# remote.net
KiCad netlist of a schematic drawn in EAGLE
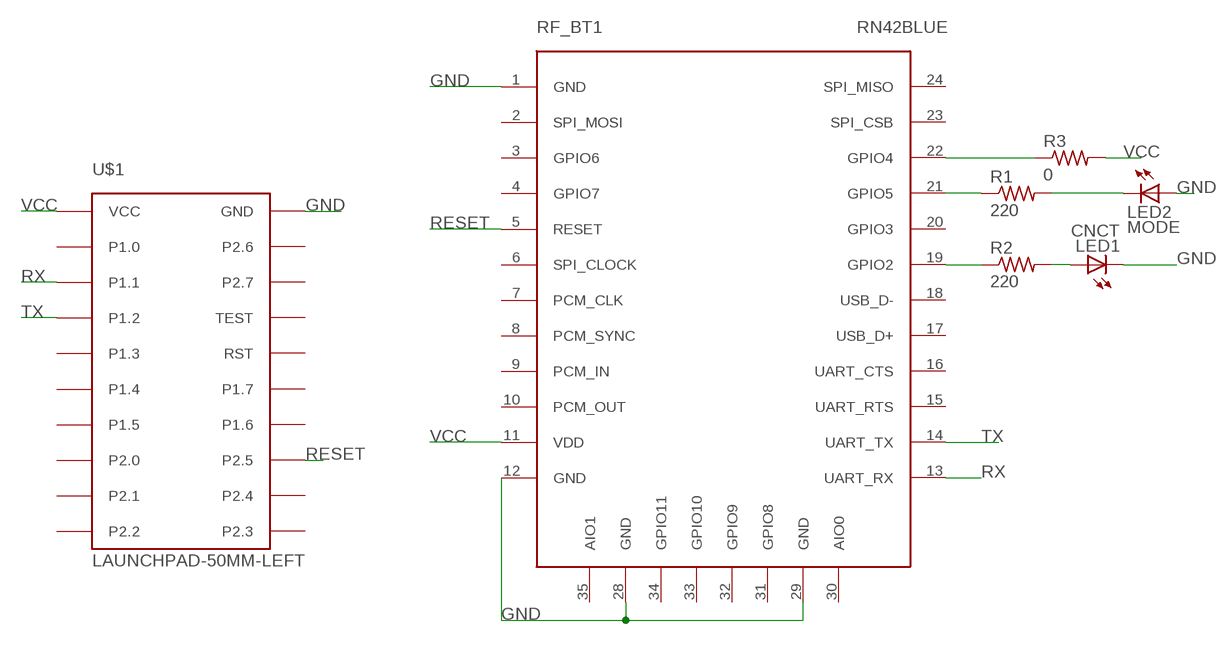
[diagram p0: schematic, sheet 1]

(export (version "E")
  (design (tool "Eeschema 10.0.6"))
  (components
    (comp (ref "LED1")
      (value "CNCT")
      (footprint "eagle-import:CHIPLED_0603")
      (libsource (lib "eagle-import") (part "LEDCHIPLED_0603"))
    )
    (comp (ref "LED2")
      (value "MODE")
      (footprint "eagle-import:CHIPLED_0603")
      (libsource (lib "eagle-import") (part "LEDCHIPLED_0603"))
    )
    (comp (ref "R1")
      (value "220")
      (footprint "eagle-import:R0603")
      (libsource (lib "eagle-import") (part "R-US_R0603"))
    )
    (comp (ref "R2")
      (value "220")
      (footprint "eagle-import:R0603")
      (libsource (lib "eagle-import") (part "R-US_R0603"))
    )
    (comp (ref "R3")
      (value "0")
      (footprint "eagle-import:R0603")
      (libsource (lib "eagle-import") (part "R-US_R0603"))
    )
    (comp (ref "RF_BT1")
      (value "RN42BLUE")
      (footprint "eagle-import:RN42_CUST_PAK")
      (libsource (lib "eagle-import") (part "RN42BLUE"))
    )
    (comp (ref "U$1")
      (value "LAUNCHPAD-50MM-LEFT")
      (footprint "eagle-import:LAUNCHPAD-50MM-LEFT")
      (libsource (lib "eagle-import") (part "LAUNCHPAD-50MM-LEFT"))
    )
  )
  (nets
    (net (code "1") (name "/GND") (class "Default")
      (node (ref "LED1") (pin "C") (pinfunction "C_C") (pintype "passive"))
      (node (ref "LED2") (pin "A") (pinfunction "A_A") (pintype "passive"))
      (node (ref "RF_BT1") (pin "1") (pinfunction "GND_1") (pintype "power_in"))
      (node (ref "RF_BT1") (pin "12") (pinfunction "GND_12") (pintype "power_in"))
      (node (ref "RF_BT1") (pin "28") (pinfunction "GND_28") (pintype "power_in"))
      (node (ref "RF_BT1") (pin "29") (pinfunction "GND_29") (pintype "power_in"))
      (node (ref "U$1") (pin "GND") (pinfunction "GND_GND") (pintype "power_in"))
    )
    (net (code "2") (name "/RESET") (class "Default")
      (node (ref "RF_BT1") (pin "5") (pinfunction "RESET_5") (pintype "bidirectional"))
      (node (ref "U$1") (pin "P2.5") (pinfunction "P2.5_P2.5") (pintype "bidirectional"))
    )
    (net (code "3") (name "/RX") (class "Default")
      (node (ref "RF_BT1") (pin "13") (pinfunction "UART_RX_13") (pintype "bidirectional"))
      (node (ref "U$1") (pin "P1.1") (pinfunction "P1.1_P1.1") (pintype "bidirectional"))
    )
    (net (code "4") (name "/TX") (class "Default")
      (node (ref "RF_BT1") (pin "14") (pinfunction "UART_TX_14") (pintype "bidirectional"))
      (node (ref "U$1") (pin "P1.2") (pinfunction "P1.2_P1.2") (pintype "bidirectional"))
    )
    (net (code "5") (name "/VCC") (class "Default")
      (node (ref "R3") (pin "2") (pinfunction "2_2") (pintype "passive"))
      (node (ref "RF_BT1") (pin "11") (pinfunction "VDD_11") (pintype "power_in"))
      (node (ref "U$1") (pin "VCC") (pinfunction "VCC_VCC") (pintype "power_in"))
    )
    (net (code "6") (name "Net-(LED1-PadA)") (class "Default")
      (node (ref "LED1") (pin "A") (pinfunction "A_A") (pintype "passive"))
      (node (ref "R2") (pin "2") (pinfunction "2_2") (pintype "passive"))
    )
    (net (code "7") (name "Net-(LED2-PadC)") (class "Default")
      (node (ref "LED2") (pin "C") (pinfunction "C_C") (pintype "passive"))
      (node (ref "R1") (pin "2") (pinfunction "2_2") (pintype "passive"))
    )
    (net (code "8") (name "Net-(RF_BT1-GPIO2)") (class "Default")
      (node (ref "R2") (pin "1") (pinfunction "1_1") (pintype "passive"))
      (node (ref "RF_BT1") (pin "19") (pinfunction "GPIO2_19") (pintype "bidirectional"))
    )
    (net (code "9") (name "Net-(RF_BT1-GPIO4)") (class "Default")
      (node (ref "R3") (pin "1") (pinfunction "1_1") (pintype "passive"))
      (node (ref "RF_BT1") (pin "22") (pinfunction "GPIO4_22") (pintype "bidirectional"))
    )
    (net (code "10") (name "Net-(RF_BT1-GPIO5)") (class "Default")
      (node (ref "R1") (pin "1") (pinfunction "1_1") (pintype "passive"))
      (node (ref "RF_BT1") (pin "21") (pinfunction "GPIO5_21") (pintype "bidirectional"))
    )
    (net (code "11") (name "unconnected-(RF_BT1-AIO0-Pad30)") (class "Default")
      (node (ref "RF_BT1") (pin "30") (pinfunction "AIO0_30") (pintype "bidirectional"))
    )
    (net (code "12") (name "unconnected-(RF_BT1-AIO1-Pad35)") (class "Default")
      (node (ref "RF_BT1") (pin "35") (pinfunction "AIO1_35") (pintype "bidirectional"))
    )
    (net (code "13") (name "unconnected-(RF_BT1-GPIO3-Pad20)") (class "Default")
      (node (ref "RF_BT1") (pin "20") (pinfunction "GPIO3_20") (pintype "bidirectional"))
    )
    (net (code "14") (name "unconnected-(RF_BT1-GPIO6-Pad3)") (class "Default")
      (node (ref "RF_BT1") (pin "3") (pinfunction "GPIO6_3") (pintype "bidirectional"))
    )
    (net (code "15") (name "unconnected-(RF_BT1-GPIO7-Pad4)") (class "Default")
      (node (ref "RF_BT1") (pin "4") (pinfunction "GPIO7_4") (pintype "bidirectional"))
    )
    (net (code "16") (name "unconnected-(RF_BT1-GPIO8-Pad31)") (class "Default")
      (node (ref "RF_BT1") (pin "31") (pinfunction "GPIO8_31") (pintype "bidirectional"))
    )
    (net (code "17") (name "unconnected-(RF_BT1-GPIO9-Pad32)") (class "Default")
      (node (ref "RF_BT1") (pin "32") (pinfunction "GPIO9_32") (pintype "bidirectional"))
    )
    (net (code "18") (name "unconnected-(RF_BT1-GPIO10-Pad33)") (class "Default")
      (node (ref "RF_BT1") (pin "33") (pinfunction "GPIO10_33") (pintype "bidirectional"))
    )
    (net (code "19") (name "unconnected-(RF_BT1-GPIO11-Pad34)") (class "Default")
      (node (ref "RF_BT1") (pin "34") (pinfunction "GPIO11_34") (pintype "bidirectional"))
    )
    (net (code "20") (name "unconnected-(RF_BT1-PCM_CLK-Pad7)") (class "Default")
      (node (ref "RF_BT1") (pin "7") (pinfunction "PCM_CLK_7") (pintype "bidirectional"))
    )
    (net (code "21") (name "unconnected-(RF_BT1-PCM_IN-Pad9)") (class "Default")
      (node (ref "RF_BT1") (pin "9") (pinfunction "PCM_IN_9") (pintype "bidirectional"))
    )
    (net (code "22") (name "unconnected-(RF_BT1-PCM_OUT-Pad10)") (class "Default")
      (node (ref "RF_BT1") (pin "10") (pinfunction "PCM_OUT_10") (pintype "bidirectional"))
    )
    (net (code "23") (name "unconnected-(RF_BT1-PCM_SYNC-Pad8)") (class "Default")
      (node (ref "RF_BT1") (pin "8") (pinfunction "PCM_SYNC_8") (pintype "bidirectional"))
    )
    (net (code "24") (name "unconnected-(RF_BT1-SPI_CLOCK-Pad6)") (class "Default")
      (node (ref "RF_BT1") (pin "6") (pinfunction "SPI_CLOCK_6") (pintype "input"))
    )
    (net (code "25") (name "unconnected-(RF_BT1-SPI_CSB-Pad23)") (class "Default")
      (node (ref "RF_BT1") (pin "23") (pinfunction "SPI_CSB_23") (pintype "bidirectional"))
    )
    (net (code "26") (name "unconnected-(RF_BT1-SPI_MISO-Pad24)") (class "Default")
      (node (ref "RF_BT1") (pin "24") (pinfunction "SPI_MISO_24") (pintype "bidirectional"))
    )
    (net (code "27") (name "unconnected-(RF_BT1-SPI_MOSI-Pad2)") (class "Default")
      (node (ref "RF_BT1") (pin "2") (pinfunction "SPI_MOSI_2") (pintype "bidirectional"))
    )
    (net (code "28") (name "unconnected-(RF_BT1-UART_CTS-Pad16)") (class "Default")
      (node (ref "RF_BT1") (pin "16") (pinfunction "UART_CTS_16") (pintype "bidirectional"))
    )
    (net (code "29") (name "unconnected-(RF_BT1-UART_RTS-Pad15)") (class "Default")
      (node (ref "RF_BT1") (pin "15") (pinfunction "UART_RTS_15") (pintype "bidirectional"))
    )
    (net (code "30") (name "unconnected-(RF_BT1-USB_D+-Pad17)") (class "Default")
      (node (ref "RF_BT1") (pin "17") (pinfunction "USB_D+_17") (pintype "bidirectional"))
    )
    (net (code "31") (name "unconnected-(RF_BT1-USB_D--Pad18)") (class "Default")
      (node (ref "RF_BT1") (pin "18") (pinfunction "USB_D-_18") (pintype "bidirectional"))
    )
    (net (code "32") (name "unconnected-(U$1-PadP1.0)") (class "Default")
      (node (ref "U$1") (pin "P1.0") (pinfunction "P1.0_P1.0") (pintype "bidirectional"))
    )
    (net (code "33") (name "unconnected-(U$1-PadP1.3)") (class "Default")
      (node (ref "U$1") (pin "P1.3") (pinfunction "P1.3_P1.3") (pintype "bidirectional"))
    )
    (net (code "34") (name "unconnected-(U$1-PadP1.4)") (class "Default")
      (node (ref "U$1") (pin "P1.4") (pinfunction "P1.4_P1.4") (pintype "bidirectional"))
    )
    (net (code "35") (name "unconnected-(U$1-PadP1.5)") (class "Default")
      (node (ref "U$1") (pin "P1.5") (pinfunction "P1.5_P1.5") (pintype "bidirectional"))
    )
    (net (code "36") (name "unconnected-(U$1-PadP1.6)") (class "Default")
      (node (ref "U$1") (pin "P1.6") (pinfunction "P1.6_P1.6") (pintype "bidirectional"))
    )
    (net (code "37") (name "unconnected-(U$1-PadP1.7)") (class "Default")
      (node (ref "U$1") (pin "P1.7") (pinfunction "P1.7_P1.7") (pintype "bidirectional"))
    )
    (net (code "38") (name "unconnected-(U$1-PadP2.0)") (class "Default")
      (node (ref "U$1") (pin "P2.0") (pinfunction "P2.0_P2.0") (pintype "bidirectional"))
    )
    (net (code "39") (name "unconnected-(U$1-PadP2.1)") (class "Default")
      (node (ref "U$1") (pin "P2.1") (pinfunction "P2.1_P2.1") (pintype "bidirectional"))
    )
    (net (code "40") (name "unconnected-(U$1-PadP2.2)") (class "Default")
      (node (ref "U$1") (pin "P2.2") (pinfunction "P2.2_P2.2") (pintype "bidirectional"))
    )
    (net (code "41") (name "unconnected-(U$1-PadP2.3)") (class "Default")
      (node (ref "U$1") (pin "P2.3") (pinfunction "P2.3_P2.3") (pintype "bidirectional"))
    )
    (net (code "42") (name "unconnected-(U$1-PadP2.4)") (class "Default")
      (node (ref "U$1") (pin "P2.4") (pinfunction "P2.4_P2.4") (pintype "bidirectional"))
    )
    (net (code "43") (name "unconnected-(U$1-PadP2.6)") (class "Default")
      (node (ref "U$1") (pin "P2.6") (pinfunction "P2.6_P2.6") (pintype "bidirectional"))
    )
    (net (code "44") (name "unconnected-(U$1-PadP2.7)") (class "Default")
      (node (ref "U$1") (pin "P2.7") (pinfunction "P2.7_P2.7") (pintype "bidirectional"))
    )
    (net (code "45") (name "unconnected-(U$1-PadRST)") (class "Default")
      (node (ref "U$1") (pin "RST") (pinfunction "RST_RST") (pintype "bidirectional"))
    )
    (net (code "46") (name "unconnected-(U$1-PadTEST)") (class "Default")
      (node (ref "U$1") (pin "TEST") (pinfunction "TEST_TEST") (pintype "bidirectional"))
    )
  )
)
